# 3x8.net
KiCad netlist of a schematic drawn in Altium Designer
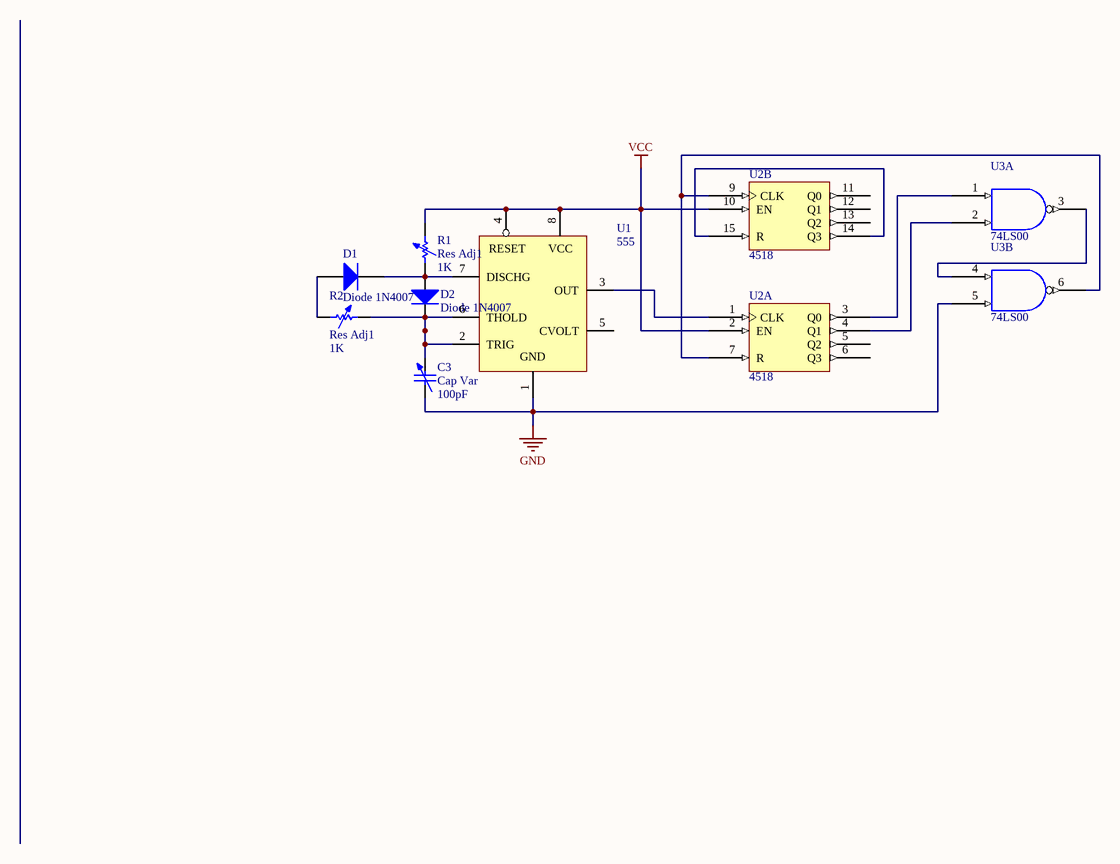
[diagram p0: 3x8.SchDoc]

(export (version "E")
  (design (tool "Eeschema 10.0.6"))
  (components
    (comp (ref "C3")
      (value "Cap Var")
      (footprint "C1210_N")
      (description "Variable or Adjustable Capacitor")
      (fields (field (name "ALTIUM_VALUE") "100pF") (field (name "PUBLISHER") "Altium Limited"))
      (libsource (lib "Miscellaneous Devices") (part "Cap Var"))
    )
    (comp (ref "D1")
      (value "Diode 1N4007")
      (footprint "DO-41")
      (description "1 Amp General Purpose Rectifier")
      (fields (field (name "PUBLISHER") "Altium Limited"))
      (libsource (lib "Miscellaneous Devices") (part "Diode 1N4007"))
    )
    (comp (ref "D2")
      (value "Diode 1N4007")
      (footprint "DO-41")
      (description "1 Amp General Purpose Rectifier")
      (fields (field (name "PUBLISHER") "Altium Limited"))
      (libsource (lib "Miscellaneous Devices") (part "Diode 1N4007"))
    )
    (comp (ref "R1")
      (value "Res Adj1")
      (footprint "AXIAL-0.7")
      (description "Variable Resistor")
      (fields (field (name "ALTIUM_VALUE") "1K") (field (name "PUBLISHER") "Altium Limited"))
      (libsource (lib "Miscellaneous Devices") (part "Res Adj1"))
    )
    (comp (ref "R2")
      (value "Res Adj1")
      (footprint "AXIAL-0.7")
      (description "Variable Resistor")
      (fields (field (name "ALTIUM_VALUE") "1K") (field (name "PUBLISHER") "Altium Limited"))
      (libsource (lib "Miscellaneous Devices") (part "Res Adj1"))
    )
    (comp (ref "U1") (value "555") (description "Timer") (libsource (lib "555") (part "555")))
    (comp (ref "U2") (value "4518") (footprint "DIP-16") (libsource (lib "CD4000系列IC") (part "4518")))
    (comp (ref "U3") (value "74LS00") (footprint "DIP-14") (libsource (lib "TTL74系列IC") (part "74LS00")))
  )
  (nets
    (net (code "1") (name "GND") (class "Default")
      (node (ref "C3") (pin "1") (pinfunction "1_1") (pintype "passive"))
      (node (ref "U1") (pin "1") (pinfunction "GND_1") (pintype "passive"))
      (node (ref "U2") (pin "8") (pinfunction "GND_8") (pintype "power_in"))
      (node (ref "U3") (pin "5") (pintype "input"))
      (node (ref "U3") (pin "7") (pinfunction "GND_7") (pintype "power_in"))
    )
    (net (code "2") (name "Net-(D1-A)") (class "Default")
      (node (ref "D1") (pin "1") (pinfunction "A_1") (pintype "passive"))
      (node (ref "R2") (pin "1") (pinfunction "1_1") (pintype "passive"))
    )
    (net (code "3") (name "Net-(D1-K)") (class "Default")
      (node (ref "D1") (pin "2") (pinfunction "K_2") (pintype "passive"))
      (node (ref "R1") (pin "1") (pinfunction "1_1") (pintype "passive"))
      (node (ref "U1") (pin "7") (pinfunction "DISCHG_7") (pintype "passive"))
    )
    (net (code "4") (name "Net-(D2-K)") (class "Default")
      (node (ref "C3") (pin "2") (pinfunction "2_2") (pintype "passive"))
      (node (ref "D2") (pin "2") (pinfunction "K_2") (pintype "passive"))
      (node (ref "R2") (pin "2") (pinfunction "2_2") (pintype "passive"))
      (node (ref "U1") (pin "2") (pinfunction "TRIG_2") (pintype "passive"))
      (node (ref "U1") (pin "6") (pinfunction "THOLD_6") (pintype "passive"))
    )
    (net (code "5") (name "Net-(U1-OUT)") (class "Default")
      (node (ref "U1") (pin "3") (pinfunction "OUT_3") (pintype "passive"))
      (node (ref "U2") (pin "1") (pinfunction "CLK_1") (pintype "input"))
    )
    (net (code "6") (name "Net-(U2A-Q0)") (class "Default")
      (node (ref "U2") (pin "3") (pinfunction "Q0_3") (pintype "output"))
      (node (ref "U3") (pin "1") (pintype "input"))
    )
    (net (code "7") (name "Net-(U2A-Q1)") (class "Default")
      (node (ref "U2") (pin "4") (pinfunction "Q1_4") (pintype "output"))
      (node (ref "U3") (pin "2") (pintype "input"))
    )
    (net (code "8") (name "Net-(U2A-R)") (class "Default")
      (node (ref "U2") (pin "7") (pinfunction "R_7") (pintype "input"))
      (node (ref "U2") (pin "9") (pinfunction "CLK_9") (pintype "input"))
      (node (ref "U3") (pin "6") (pintype "output"))
    )
    (net (code "9") (name "Net-(U2B-Q3)") (class "Default")
      (node (ref "U2") (pin "14") (pinfunction "Q3_14") (pintype "output"))
      (node (ref "U2") (pin "15") (pinfunction "R_15") (pintype "input"))
    )
    (net (code "10") (name "Net-(U3-Pad3)") (class "Default")
      (node (ref "U3") (pin "3") (pintype "output"))
      (node (ref "U3") (pin "4") (pintype "input"))
    )
    (net (code "11") (name "VCC") (class "Default")
      (node (ref "R1") (pin "2") (pinfunction "2_2") (pintype "passive"))
      (node (ref "U1") (pin "4") (pinfunction "RESET_4") (pintype "passive"))
      (node (ref "U1") (pin "8") (pinfunction "VCC_8") (pintype "passive"))
      (node (ref "U2") (pin "10") (pinfunction "EN_10") (pintype "input"))
      (node (ref "U2") (pin "16") (pinfunction "VCC_16") (pintype "power_in"))
      (node (ref "U2") (pin "2") (pinfunction "EN_2") (pintype "input"))
      (node (ref "U3") (pin "14") (pinfunction "VCC_14") (pintype "power_in"))
    )
    (net (code "12") (name "unconnected-(D2-A-Pad1)") (class "Default")
      (node (ref "D2") (pin "1") (pinfunction "A_1") (pintype "passive"))
    )
    (net (code "13") (name "unconnected-(U1-CVOLT-Pad5)") (class "Default")
      (node (ref "U1") (pin "5") (pinfunction "CVOLT_5") (pintype "passive"))
    )
    (net (code "14") (name "unconnected-(U2A-Q2-Pad5)") (class "Default")
      (node (ref "U2") (pin "5") (pinfunction "Q2_5") (pintype "output"))
    )
    (net (code "15") (name "unconnected-(U2A-Q3-Pad6)") (class "Default")
      (node (ref "U2") (pin "6") (pinfunction "Q3_6") (pintype "output"))
    )
    (net (code "16") (name "unconnected-(U2B-Q0-Pad11)") (class "Default")
      (node (ref "U2") (pin "11") (pinfunction "Q0_11") (pintype "output"))
    )
    (net (code "17") (name "unconnected-(U2B-Q1-Pad12)") (class "Default")
      (node (ref "U2") (pin "12") (pinfunction "Q1_12") (pintype "output"))
    )
    (net (code "18") (name "unconnected-(U2B-Q2-Pad13)") (class "Default")
      (node (ref "U2") (pin "13") (pinfunction "Q2_13") (pintype "output"))
    )
  )
)
